# BreadBox.net
KiCad netlist of a schematic drawn in EAGLE
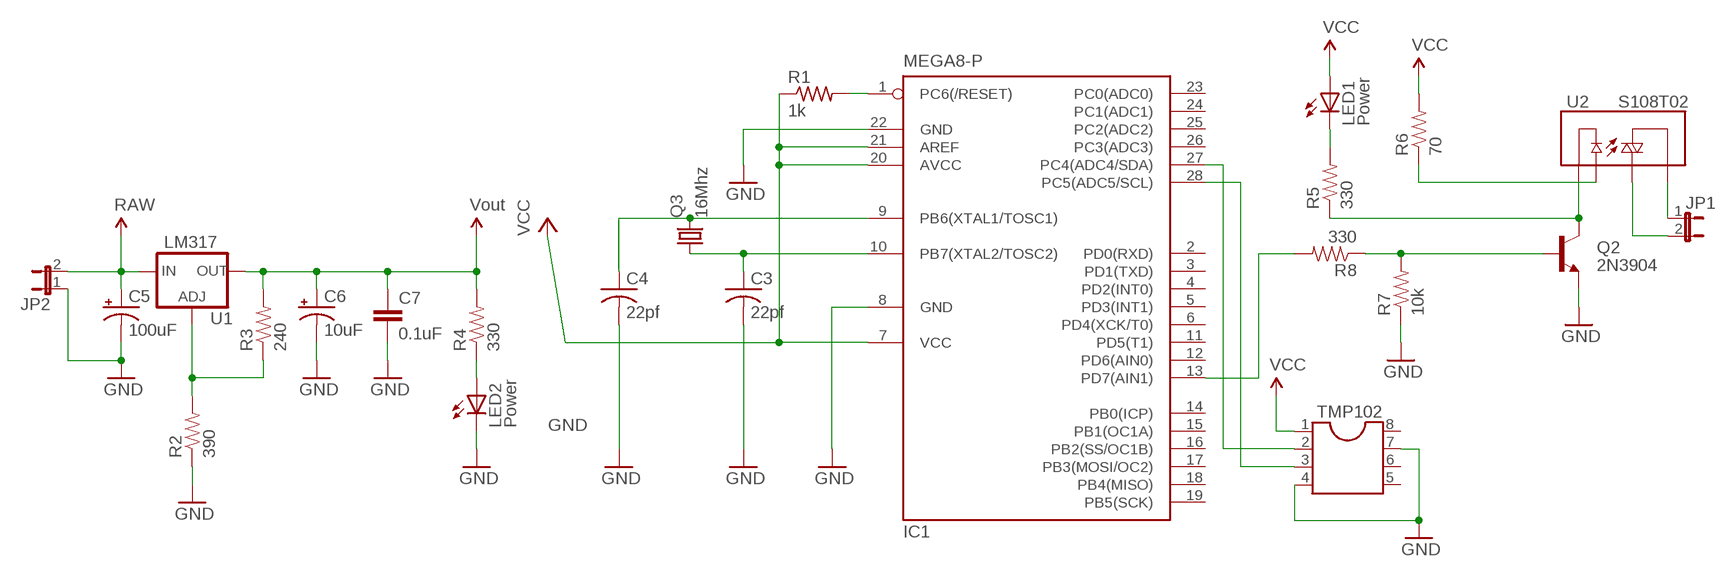
[diagram p0: schematic, sheet 1]

(export (version "E")
  (design (tool "Eeschema 10.0.6"))
  (components
    (comp (ref "C3")
      (value "22pf")
      (footprint "eagle-import:C025-024X044")
      (libsource (lib "eagle-import") (part "C-US025-024X044"))
    )
    (comp (ref "C4")
      (value "22pf")
      (footprint "eagle-import:C025-024X044")
      (libsource (lib "eagle-import") (part "C-US025-024X044"))
    )
    (comp (ref "C5")
      (value "100uF")
      (footprint "eagle-import:CPOL-RADIAL-100UF-25V")
      (libsource (lib "eagle-import") (part "CAP_POLPTH1"))
    )
    (comp (ref "C6")
      (value "10uF")
      (footprint "eagle-import:CPOL-RADIAL-10UF-25V")
      (libsource (lib "eagle-import") (part "CAP_POLPTH2"))
    )
    (comp (ref "C7")
      (value "0.1uF")
      (footprint "eagle-import:CAP-PTH-SMALL2")
      (libsource (lib "eagle-import") (part "CAPPTH2"))
    )
    (comp (ref "IC1")
      (value "MEGA8-P")
      (footprint "eagle-import:DIL28-3")
      (libsource (lib "eagle-import") (part "MEGA8-P"))
    )
    (comp (ref "JP1")
      (value "JP1E")
      (footprint "eagle-import:JP1")
      (libsource (lib "eagle-import") (part "JP1E"))
    )
    (comp (ref "JP2")
      (value "JP1E")
      (footprint "eagle-import:JP1")
      (libsource (lib "eagle-import") (part "JP1E"))
    )
    (comp (ref "LED1")
      (value "Power")
      (footprint "eagle-import:LED5MM")
      (libsource (lib "eagle-import") (part "LED5MM"))
    )
    (comp (ref "LED2")
      (value "Power")
      (footprint "eagle-import:LED5MM")
      (libsource (lib "eagle-import") (part "LED5MM"))
    )
    (comp (ref "Q2")
      (value "2N3904")
      (footprint "eagle-import:TO-92")
      (libsource (lib "eagle-import") (part "TRANSISTOR_NPNTO92"))
    )
    (comp (ref "Q3")
      (value "16Mhz")
      (footprint "eagle-import:HC18U-V")
      (libsource (lib "eagle-import") (part "CRYSTALHC18U-V"))
    )
    (comp (ref "R1")
      (value "1k")
      (footprint "eagle-import:0207_10")
      (libsource (lib "eagle-import") (part "R-US_0207/10"))
    )
    (comp (ref "R2")
      (value "390")
      (footprint "eagle-import:AXIAL-0.3")
      (libsource (lib "eagle-import") (part "RESISTORPTH1"))
    )
    (comp (ref "R3")
      (value "240")
      (footprint "eagle-import:AXIAL-0.3")
      (libsource (lib "eagle-import") (part "RESISTORPTH1"))
    )
    (comp (ref "R4")
      (value "330")
      (footprint "eagle-import:AXIAL-0.3")
      (libsource (lib "eagle-import") (part "RESISTORPTH1"))
    )
    (comp (ref "R5")
      (value "330")
      (footprint "eagle-import:AXIAL-0.3")
      (libsource (lib "eagle-import") (part "RESISTORPTH1"))
    )
    (comp (ref "R6")
      (value "70")
      (footprint "eagle-import:AXIAL-0.3")
      (libsource (lib "eagle-import") (part "RESISTORPTH1"))
    )
    (comp (ref "R7")
      (value "10k")
      (footprint "eagle-import:AXIAL-0.3")
      (libsource (lib "eagle-import") (part "RESISTORPTH1"))
    )
    (comp (ref "R8")
      (value "330")
      (footprint "eagle-import:AXIAL-0.3")
      (libsource (lib "eagle-import") (part "RESISTORPTH1"))
    )
    (comp (ref "TMP102")
      (value "DIL8S")
      (footprint "eagle-import:SOCKET-08")
      (libsource (lib "eagle-import") (part "DIL8S"))
    )
    (comp (ref "U1")
      (value "LM317")
      (footprint "eagle-import:TO220-ADJ")
      (libsource (lib "eagle-import") (part "V_REG_317SINK"))
    )
    (comp (ref "U2")
      (value "S108T02")
      (footprint "eagle-import:RELAY-S108T02")
      (libsource (lib "eagle-import") (part "RELAY-SOLIDSTATEPTH"))
    )
  )
  (nets
    (net (code "1") (name "GND") (class "Default")
      (node (ref "C3") (pin "2") (pinfunction "2_2") (pintype "passive"))
      (node (ref "C4") (pin "2") (pinfunction "2_2") (pintype "passive"))
      (node (ref "C5") (pin "2") (pinfunction "-_2") (pintype "passive"))
      (node (ref "C6") (pin "2") (pinfunction "-_2") (pintype "passive"))
      (node (ref "C7") (pin "2") (pinfunction "2_2") (pintype "passive"))
      (node (ref "IC1") (pin "22") (pinfunction "GND_22") (pintype "power_in"))
      (node (ref "IC1") (pin "8") (pinfunction "GND_8") (pintype "power_in"))
      (node (ref "JP2") (pin "1") (pinfunction "1_1") (pintype "passive"))
      (node (ref "LED2") (pin "K") (pinfunction "C_K") (pintype "passive"))
      (node (ref "Q2") (pin "1") (pinfunction "E_1") (pintype "passive"))
      (node (ref "R2") (pin "P$1") (pinfunction "1_P$1") (pintype "passive"))
      (node (ref "R7") (pin "P$1") (pinfunction "1_P$1") (pintype "passive"))
      (node (ref "TMP102") (pin "4") (pinfunction "4_4") (pintype "passive"))
      (node (ref "TMP102") (pin "7") (pinfunction "7_7") (pintype "passive"))
    )
    (net (code "2") (name "Net-(IC1-PB6(XTAL1{slash}TOSC1))") (class "Default")
      (node (ref "C4") (pin "1") (pinfunction "1_1") (pintype "passive"))
      (node (ref "IC1") (pin "9") (pinfunction "PB6(XTAL1/TOSC1)_9") (pintype "bidirectional"))
      (node (ref "Q3") (pin "2") (pinfunction "2_2") (pintype "passive"))
    )
    (net (code "3") (name "Net-(IC1-PB7(XTAL2{slash}TOSC2))") (class "Default")
      (node (ref "C3") (pin "1") (pinfunction "1_1") (pintype "passive"))
      (node (ref "IC1") (pin "10") (pinfunction "PB7(XTAL2/TOSC2)_10") (pintype "bidirectional"))
      (node (ref "Q3") (pin "1") (pinfunction "1_1") (pintype "passive"))
    )
    (net (code "4") (name "Net-(IC1-PC4(ADC4{slash}SDA))") (class "Default")
      (node (ref "IC1") (pin "27") (pinfunction "PC4(ADC4/SDA)_27") (pintype "bidirectional"))
      (node (ref "TMP102") (pin "2") (pinfunction "2_2") (pintype "passive"))
    )
    (net (code "5") (name "Net-(IC1-PC5(ADC5{slash}SCL))") (class "Default")
      (node (ref "IC1") (pin "28") (pinfunction "PC5(ADC5/SCL)_28") (pintype "bidirectional"))
      (node (ref "TMP102") (pin "3") (pinfunction "3_3") (pintype "passive"))
    )
    (net (code "6") (name "Net-(IC1-PC6({slash}RESET))") (class "Default")
      (node (ref "IC1") (pin "1") (pinfunction "PC6(/RESET)_1") (pintype "bidirectional"))
      (node (ref "R1") (pin "2") (pinfunction "2_2") (pintype "passive"))
    )
    (net (code "7") (name "Net-(IC1-PD7(AIN1))") (class "Default")
      (node (ref "IC1") (pin "13") (pinfunction "PD7(AIN1)_13") (pintype "bidirectional"))
      (node (ref "R8") (pin "P$2") (pinfunction "2_P$2") (pintype "passive"))
    )
    (net (code "8") (name "Net-(LED1-C)") (class "Default")
      (node (ref "LED1") (pin "K") (pinfunction "C_K") (pintype "passive"))
      (node (ref "R5") (pin "P$2") (pinfunction "2_P$2") (pintype "passive"))
    )
    (net (code "9") (name "Net-(Q2-B)") (class "Default")
      (node (ref "Q2") (pin "2") (pinfunction "B_2") (pintype "passive"))
      (node (ref "R7") (pin "P$2") (pinfunction "2_P$2") (pintype "passive"))
      (node (ref "R8") (pin "P$1") (pinfunction "1_P$1") (pintype "passive"))
    )
    (net (code "10") (name "Net-(Q2-C)") (class "Default")
      (node (ref "Q2") (pin "3") (pinfunction "C_3") (pintype "passive"))
      (node (ref "R5") (pin "P$1") (pinfunction "1_P$1") (pintype "passive"))
      (node (ref "U2") (pin "4") (pinfunction "-_4") (pintype "bidirectional"))
    )
    (net (code "11") (name "Net-(R2-2)") (class "Default")
      (node (ref "R2") (pin "P$2") (pinfunction "2_P$2") (pintype "passive"))
      (node (ref "R3") (pin "P$1") (pinfunction "1_P$1") (pintype "passive"))
      (node (ref "U1") (pin "ADJ") (pinfunction "ADJ_ADJ") (pintype "input"))
    )
    (net (code "12") (name "Net-(R4-1)") (class "Default")
      (node (ref "LED2") (pin "A") (pinfunction "A_A") (pintype "passive"))
      (node (ref "R4") (pin "P$1") (pinfunction "1_P$1") (pintype "passive"))
    )
    (net (code "13") (name "Net-(R6-1)") (class "Default")
      (node (ref "R6") (pin "P$1") (pinfunction "1_P$1") (pintype "passive"))
      (node (ref "U2") (pin "3") (pinfunction "+_3") (pintype "bidirectional"))
    )
    (net (code "14") (name "Net-(U2-T1)") (class "Default")
      (node (ref "JP1") (pin "1") (pinfunction "1_1") (pintype "passive"))
      (node (ref "U2") (pin "1") (pinfunction "T1_1") (pintype "bidirectional"))
    )
    (net (code "15") (name "Net-(U2-T2)") (class "Default")
      (node (ref "JP1") (pin "2") (pinfunction "2_2") (pintype "passive"))
      (node (ref "U2") (pin "2") (pinfunction "T2_2") (pintype "bidirectional"))
    )
    (net (code "16") (name "RAW") (class "Default")
      (node (ref "C5") (pin "1") (pinfunction "+_1") (pintype "passive"))
      (node (ref "JP2") (pin "2") (pinfunction "2_2") (pintype "passive"))
      (node (ref "U1") (pin "IN") (pinfunction "IN_IN") (pintype "input"))
    )
    (net (code "17") (name "VCC") (class "Default")
      (node (ref "C6") (pin "1") (pinfunction "+_1") (pintype "passive"))
      (node (ref "C7") (pin "1") (pinfunction "1_1") (pintype "passive"))
      (node (ref "IC1") (pin "20") (pinfunction "AVCC_20") (pintype "power_in"))
      (node (ref "IC1") (pin "21") (pinfunction "AREF_21") (pintype "passive"))
      (node (ref "IC1") (pin "7") (pinfunction "VCC_7") (pintype "power_in"))
      (node (ref "LED1") (pin "A") (pinfunction "A_A") (pintype "passive"))
      (node (ref "R1") (pin "1") (pinfunction "1_1") (pintype "passive"))
      (node (ref "R3") (pin "P$2") (pinfunction "2_P$2") (pintype "passive"))
      (node (ref "R4") (pin "P$2") (pinfunction "2_P$2") (pintype "passive"))
      (node (ref "R6") (pin "P$2") (pinfunction "2_P$2") (pintype "passive"))
      (node (ref "TMP102") (pin "1") (pinfunction "1_1") (pintype "passive"))
      (node (ref "U1") (pin "OUT") (pinfunction "OUT_OUT") (pintype "output"))
    )
    (net (code "18") (name "unconnected-(IC1-PB0(ICP)-Pad14)") (class "Default")
      (node (ref "IC1") (pin "14") (pinfunction "PB0(ICP)_14") (pintype "bidirectional"))
    )
    (net (code "19") (name "unconnected-(IC1-PB1(OC1A)-Pad15)") (class "Default")
      (node (ref "IC1") (pin "15") (pinfunction "PB1(OC1A)_15") (pintype "bidirectional"))
    )
    (net (code "20") (name "unconnected-(IC1-PB2(SS{slash}OC1B)-Pad16)") (class "Default")
      (node (ref "IC1") (pin "16") (pinfunction "PB2(SS/OC1B)_16") (pintype "bidirectional"))
    )
    (net (code "21") (name "unconnected-(IC1-PB3(MOSI{slash}OC2)-Pad17)") (class "Default")
      (node (ref "IC1") (pin "17") (pinfunction "PB3(MOSI/OC2)_17") (pintype "bidirectional"))
    )
    (net (code "22") (name "unconnected-(IC1-PB4(MISO)-Pad18)") (class "Default")
      (node (ref "IC1") (pin "18") (pinfunction "PB4(MISO)_18") (pintype "bidirectional"))
    )
    (net (code "23") (name "unconnected-(IC1-PB5(SCK)-Pad19)") (class "Default")
      (node (ref "IC1") (pin "19") (pinfunction "PB5(SCK)_19") (pintype "bidirectional"))
    )
    (net (code "24") (name "unconnected-(IC1-PC0(ADC0)-Pad23)") (class "Default")
      (node (ref "IC1") (pin "23") (pinfunction "PC0(ADC0)_23") (pintype "bidirectional"))
    )
    (net (code "25") (name "unconnected-(IC1-PC1(ADC1)-Pad24)") (class "Default")
      (node (ref "IC1") (pin "24") (pinfunction "PC1(ADC1)_24") (pintype "bidirectional"))
    )
    (net (code "26") (name "unconnected-(IC1-PC2(ADC2)-Pad25)") (class "Default")
      (node (ref "IC1") (pin "25") (pinfunction "PC2(ADC2)_25") (pintype "bidirectional"))
    )
    (net (code "27") (name "unconnected-(IC1-PC3(ADC3)-Pad26)") (class "Default")
      (node (ref "IC1") (pin "26") (pinfunction "PC3(ADC3)_26") (pintype "bidirectional"))
    )
    (net (code "28") (name "unconnected-(IC1-PD0(RXD)-Pad2)") (class "Default")
      (node (ref "IC1") (pin "2") (pinfunction "PD0(RXD)_2") (pintype "bidirectional"))
    )
    (net (code "29") (name "unconnected-(IC1-PD1(TXD)-Pad3)") (class "Default")
      (node (ref "IC1") (pin "3") (pinfunction "PD1(TXD)_3") (pintype "bidirectional"))
    )
    (net (code "30") (name "unconnected-(IC1-PD2(INT0)-Pad4)") (class "Default")
      (node (ref "IC1") (pin "4") (pinfunction "PD2(INT0)_4") (pintype "bidirectional"))
    )
    (net (code "31") (name "unconnected-(IC1-PD3(INT1)-Pad5)") (class "Default")
      (node (ref "IC1") (pin "5") (pinfunction "PD3(INT1)_5") (pintype "bidirectional"))
    )
    (net (code "32") (name "unconnected-(IC1-PD4(XCK{slash}T0)-Pad6)") (class "Default")
      (node (ref "IC1") (pin "6") (pinfunction "PD4(XCK/T0)_6") (pintype "bidirectional"))
    )
    (net (code "33") (name "unconnected-(IC1-PD5(T1)-Pad11)") (class "Default")
      (node (ref "IC1") (pin "11") (pinfunction "PD5(T1)_11") (pintype "bidirectional"))
    )
    (net (code "34") (name "unconnected-(IC1-PD6(AIN0)-Pad12)") (class "Default")
      (node (ref "IC1") (pin "12") (pinfunction "PD6(AIN0)_12") (pintype "bidirectional"))
    )
    (net (code "35") (name "unconnected-(TMP102-Pad5)") (class "Default")
      (node (ref "TMP102") (pin "5") (pinfunction "5_5") (pintype "passive"))
    )
    (net (code "36") (name "unconnected-(TMP102-Pad6)") (class "Default")
      (node (ref "TMP102") (pin "6") (pinfunction "6_6") (pintype "passive"))
    )
    (net (code "37") (name "unconnected-(TMP102-Pad8)") (class "Default")
      (node (ref "TMP102") (pin "8") (pinfunction "8_8") (pintype "passive"))
    )
  )
)
